# DebugCAN_v2.net
KiCad netlist of a schematic drawn in EAGLE
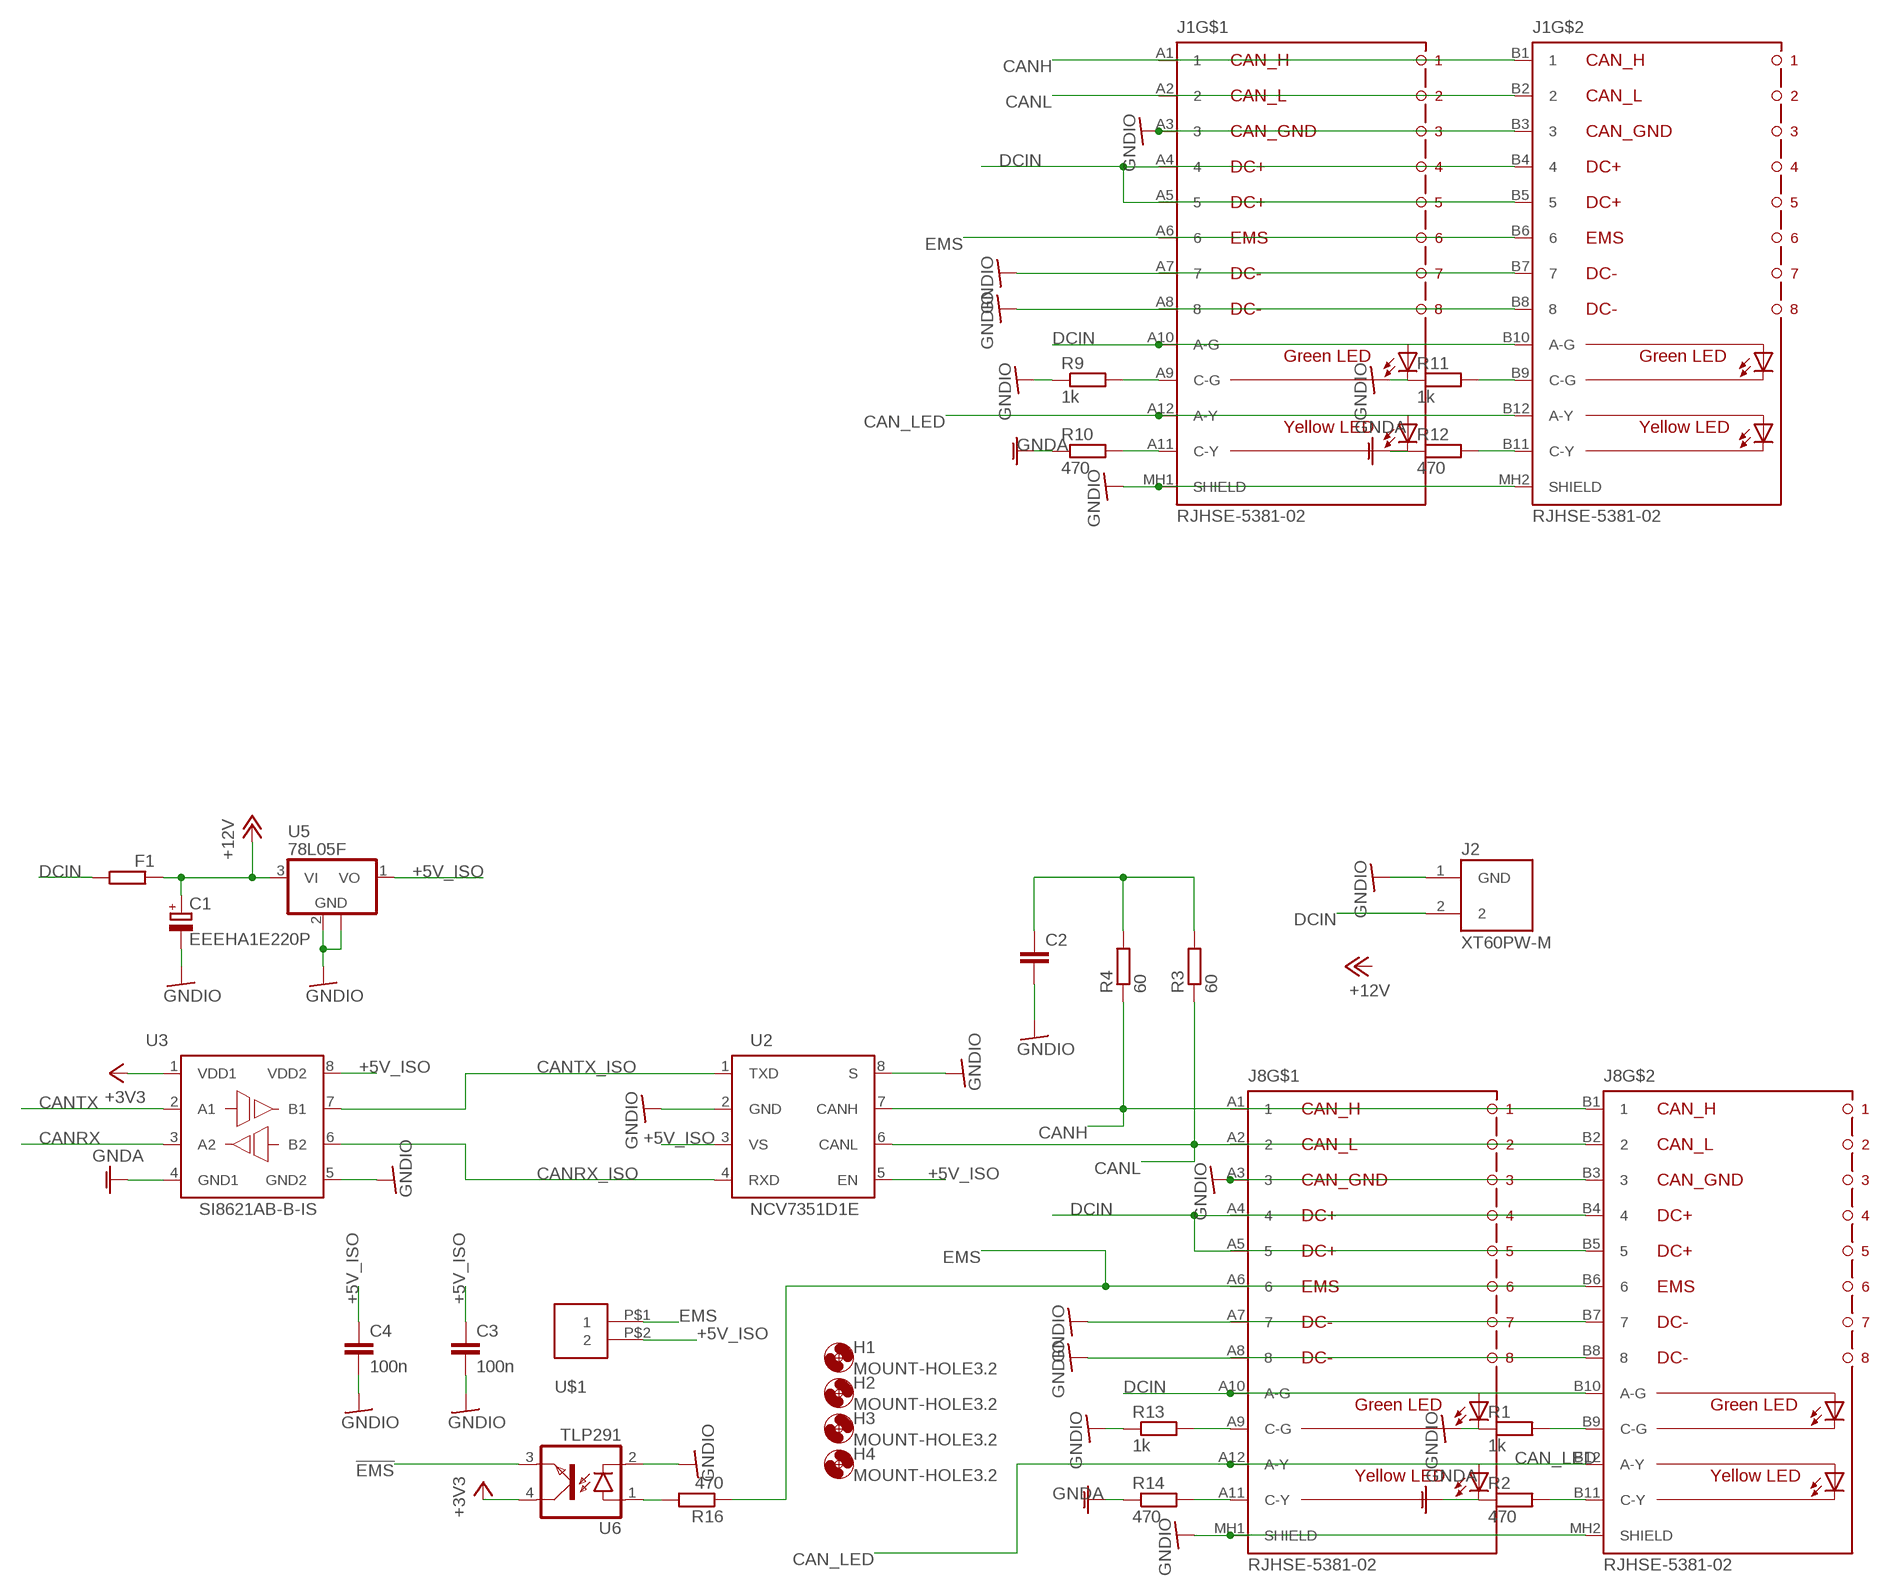
[diagram p0: schematic, sheet 1]
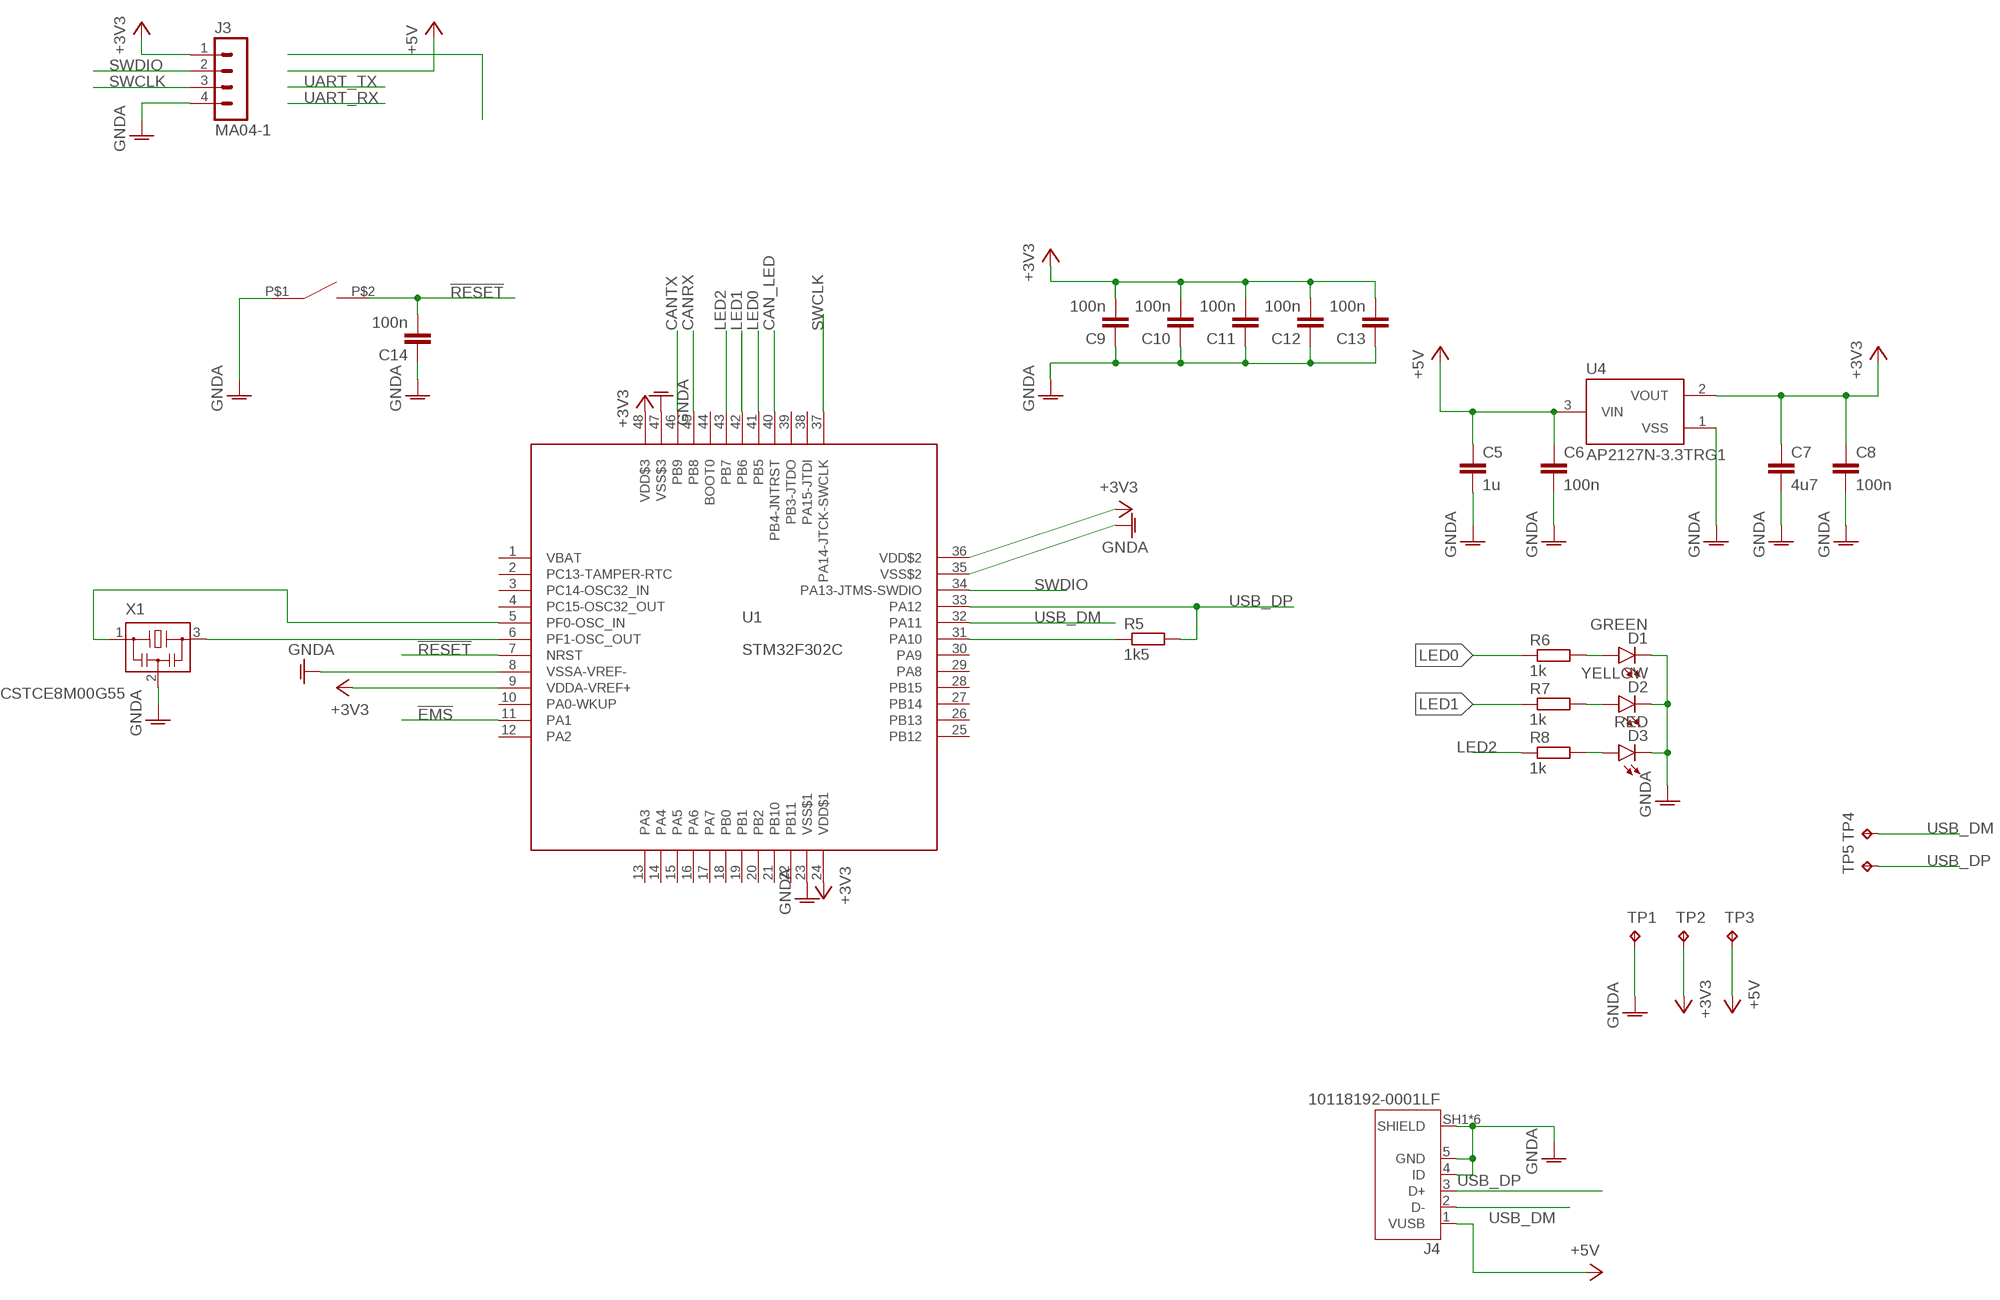
[diagram p1: schematic, sheet 2]

(export (version "E")
  (design (tool "Eeschema 10.0.6"))
  (components
    (comp (ref "C1")
      (value "EEEHA1E220P")
      (footprint "eagle-import:153CLV-0605")
      (libsource (lib "eagle-import") (part "CPOL-EU153CLV-0605"))
    )
    (comp (ref "C2")
      (value "C-EUC0603")
      (footprint "eagle-import:C0603")
      (libsource (lib "eagle-import") (part "rcl_334_C-EUC0603"))
    )
    (comp (ref "C3")
      (value "100n")
      (footprint "eagle-import:C0603")
      (libsource (lib "eagle-import") (part "rcl_334_C-EUC0603"))
    )
    (comp (ref "C4")
      (value "100n")
      (footprint "eagle-import:C0603")
      (libsource (lib "eagle-import") (part "rcl_334_C-EUC0603"))
    )
    (comp (ref "F1")
      (value "R-EU_R1206")
      (footprint "eagle-import:R1206")
      (libsource (lib "eagle-import") (part "rcl_334_R-EU_R1206"))
    )
    (comp (ref "H1")
      (value "MOUNT-HOLE3.2")
      (footprint "eagle-import:3,2")
      (libsource (lib "eagle-import") (part "MOUNT-HOLE3.2"))
    )
    (comp (ref "H2")
      (value "MOUNT-HOLE3.2")
      (footprint "eagle-import:3,2")
      (libsource (lib "eagle-import") (part "MOUNT-HOLE3.2"))
    )
    (comp (ref "H3")
      (value "MOUNT-HOLE3.2")
      (footprint "eagle-import:3,2")
      (libsource (lib "eagle-import") (part "MOUNT-HOLE3.2"))
    )
    (comp (ref "H4")
      (value "MOUNT-HOLE3.2")
      (footprint "eagle-import:3,2")
      (libsource (lib "eagle-import") (part "MOUNT-HOLE3.2"))
    )
    (comp (ref "J1")
      (value "RJHSE-5381-02")
      (footprint "eagle-import:RJHSE538102")
      (fields (field (name "MOUSER_PART_NUMBER") "523-RJHSE-5381-02"))
      (libsource (lib "eagle-import") (part "RJHSE-5381-02"))
    )
    (comp (ref "J2")
      (value "XT60PW-M")
      (footprint "eagle-import:AMASS_XT60PW-M")
      (fields (field (name "MF") "AMASS") (field (name "MP") "XT60PW-M "))
      (libsource (lib "eagle-import") (part "XT60PW-M"))
    )
    (comp (ref "J8")
      (value "RJHSE-5381-02")
      (footprint "eagle-import:RJHSE538102")
      (fields (field (name "MOUSER_PART_NUMBER") "523-RJHSE-5381-02"))
      (libsource (lib "eagle-import") (part "RJHSE-5381-02"))
    )
    (comp (ref "R1")
      (value "1k")
      (footprint "eagle-import:R0603")
      (libsource (lib "eagle-import") (part "rcl_334_R-EU_R0603"))
    )
    (comp (ref "R2")
      (value "470")
      (footprint "eagle-import:R0603")
      (libsource (lib "eagle-import") (part "rcl_334_R-EU_R0603"))
    )
    (comp (ref "R3")
      (value "60")
      (footprint "eagle-import:R0603")
      (libsource (lib "eagle-import") (part "rcl_334_R-EU_R0603"))
    )
    (comp (ref "R4")
      (value "60")
      (footprint "eagle-import:R0603")
      (libsource (lib "eagle-import") (part "rcl_334_R-EU_R0603"))
    )
    (comp (ref "R9")
      (value "1k")
      (footprint "eagle-import:R0603")
      (libsource (lib "eagle-import") (part "rcl_334_R-EU_R0603"))
    )
    (comp (ref "R10")
      (value "470")
      (footprint "eagle-import:R0603")
      (libsource (lib "eagle-import") (part "rcl_334_R-EU_R0603"))
    )
    (comp (ref "R11")
      (value "1k")
      (footprint "eagle-import:R0603")
      (libsource (lib "eagle-import") (part "rcl_334_R-EU_R0603"))
    )
    (comp (ref "R12")
      (value "470")
      (footprint "eagle-import:R0603")
      (libsource (lib "eagle-import") (part "rcl_334_R-EU_R0603"))
    )
    (comp (ref "R13")
      (value "1k")
      (footprint "eagle-import:R0603")
      (libsource (lib "eagle-import") (part "rcl_334_R-EU_R0603"))
    )
    (comp (ref "R14")
      (value "470")
      (footprint "eagle-import:R0603")
      (libsource (lib "eagle-import") (part "rcl_334_R-EU_R0603"))
    )
    (comp (ref "R16")
      (value "470")
      (footprint "eagle-import:R0603")
      (libsource (lib "eagle-import") (part "rcl_334_R-EU_R0603"))
    )
    (comp (ref "U$1")
      (value "XH-2-STRAIGHT")
      (footprint "eagle-import:CON-XH-2-STRAIGHT")
      (libsource (lib "eagle-import") (part "XH-2-STRAIGHT"))
    )
    (comp (ref "U2")
      (value "NCV7351D1E")
      (footprint "eagle-import:SO08")
      (libsource (lib "eagle-import") (part "NCV7351D1E"))
    )
    (comp (ref "U3")
      (value "SI8621AB-B-IS")
      (footprint "eagle-import:SO08")
      (libsource (lib "eagle-import") (part "SI8621AB-B-IS"))
    )
    (comp (ref "U5")
      (value "78L05F")
      (footprint "eagle-import:SOT89")
      (libsource (lib "eagle-import") (part "78LF05"))
    )
    (comp (ref "U6")
      (value "TLP291")
      (footprint "eagle-import:MINI-FLAT-4")
      (libsource (lib "eagle-import") (part "TLP291"))
    )
    (comp (ref "C5")
      (value "1u")
      (footprint "eagle-import:C0603")
      (libsource (lib "eagle-import") (part "C-EUC0603"))
    )
    (comp (ref "C6")
      (value "100n")
      (footprint "eagle-import:C0603")
      (libsource (lib "eagle-import") (part "C-EUC0603"))
    )
    (comp (ref "C7")
      (value "4u7")
      (footprint "eagle-import:C0805")
      (libsource (lib "eagle-import") (part "C-EUC0805"))
    )
    (comp (ref "C8")
      (value "100n")
      (footprint "eagle-import:C0603")
      (libsource (lib "eagle-import") (part "C-EUC0603"))
    )
    (comp (ref "C9")
      (value "100n")
      (footprint "eagle-import:C0603")
      (libsource (lib "eagle-import") (part "C-EUC0603"))
    )
    (comp (ref "C10")
      (value "100n")
      (footprint "eagle-import:C0603")
      (libsource (lib "eagle-import") (part "C-EUC0603"))
    )
    (comp (ref "C11")
      (value "100n")
      (footprint "eagle-import:C0603")
      (libsource (lib "eagle-import") (part "C-EUC0603"))
    )
    (comp (ref "C12")
      (value "100n")
      (footprint "eagle-import:C0603")
      (libsource (lib "eagle-import") (part "C-EUC0603"))
    )
    (comp (ref "C13")
      (value "100n")
      (footprint "eagle-import:C0603")
      (libsource (lib "eagle-import") (part "C-EUC0603"))
    )
    (comp (ref "C14")
      (value "100n")
      (footprint "eagle-import:C0603")
      (libsource (lib "eagle-import") (part "C-EUC0603"))
    )
    (comp (ref "D1")
      (value "GREEN")
      (footprint "eagle-import:CHIPLED_0805")
      (libsource (lib "eagle-import") (part "LEDCHIPLED_0805"))
    )
    (comp (ref "D2")
      (value "YELLOW")
      (footprint "eagle-import:CHIPLED_0805")
      (libsource (lib "eagle-import") (part "LEDCHIPLED_0805"))
    )
    (comp (ref "D3")
      (value "RED")
      (footprint "eagle-import:CHIPLED_0805")
      (libsource (lib "eagle-import") (part "LEDCHIPLED_0805"))
    )
    (comp (ref "J3")
      (value "MA04-1")
      (footprint "eagle-import:MA04-1")
      (libsource (lib "eagle-import") (part "MA04-1"))
    )
    (comp (ref "J4")
      (value "10118192-0001LF")
      (footprint "eagle-import:AMPHENOL_10118192-0001LF")
      (fields (field (name "DIGI-KEY_PART_NUMBER") "609-4613-1-ND") (field (name "MF") "Amphenol ICC"))
      (libsource (lib "eagle-import") (part "10118192-0001LF"))
    )
    (comp (ref "R5")
      (value "1k5")
      (footprint "eagle-import:R0603")
      (libsource (lib "eagle-import") (part "R-EU_R0603"))
    )
    (comp (ref "R6")
      (value "1k")
      (footprint "eagle-import:R0603")
      (libsource (lib "eagle-import") (part "R-EU_R0603"))
    )
    (comp (ref "R7")
      (value "1k")
      (footprint "eagle-import:R0603")
      (libsource (lib "eagle-import") (part "R-EU_R0603"))
    )
    (comp (ref "R8")
      (value "1k")
      (footprint "eagle-import:R0603")
      (libsource (lib "eagle-import") (part "R-EU_R0603"))
    )
    (comp (ref "S1")
      (value "SWITCH_TACTILETOP")
      (footprint "eagle-import:SWITCH_TACTILE_3X6")
      (libsource (lib "eagle-import") (part "SWITCH_TACTILETOP"))
    )
    (comp (ref "TP1")
      (value "TPB1,27")
      (footprint "eagle-import:B1,27")
      (libsource (lib "eagle-import") (part "TPB1,27"))
    )
    (comp (ref "TP2")
      (value "TPB1,27")
      (footprint "eagle-import:B1,27")
      (libsource (lib "eagle-import") (part "TPB1,27"))
    )
    (comp (ref "TP3")
      (value "TPB1,27")
      (footprint "eagle-import:B1,27")
      (libsource (lib "eagle-import") (part "TPB1,27"))
    )
    (comp (ref "TP4")
      (value "TPB1,27")
      (footprint "eagle-import:B1,27")
      (libsource (lib "eagle-import") (part "TPB1,27"))
    )
    (comp (ref "TP5")
      (value "TPB1,27")
      (footprint "eagle-import:B1,27")
      (libsource (lib "eagle-import") (part "TPB1,27"))
    )
    (comp (ref "U1")
      (value "STM32F302C")
      (footprint "eagle-import:LQFP48")
      (libsource (lib "eagle-import") (part "STM32F303C"))
    )
    (comp (ref "U4")
      (value "AP2127N-3.3TRG1")
      (footprint "eagle-import:SOT95P240X110-3")
      (libsource (lib "eagle-import") (part "XC6206"))
    )
    (comp (ref "X1")
      (value "CSTCE8M00G55")
      (footprint "eagle-import:CSTCE8M00G55")
      (libsource (lib "eagle-import") (part "CSTCE8M00G55"))
    )
  )
  (nets
    (net (code "1") (name "+3V3") (class "Default")
      (node (ref "C10") (pin "2") (pinfunction "2_2") (pintype "passive"))
      (node (ref "C11") (pin "2") (pinfunction "2_2") (pintype "passive"))
      (node (ref "C12") (pin "2") (pinfunction "2_2") (pintype "passive"))
      (node (ref "C13") (pin "2") (pinfunction "2_2") (pintype "passive"))
      (node (ref "C7") (pin "1") (pinfunction "1_1") (pintype "passive"))
      (node (ref "C8") (pin "1") (pinfunction "1_1") (pintype "passive"))
      (node (ref "C9") (pin "2") (pinfunction "2_2") (pintype "passive"))
      (node (ref "J3") (pin "1") (pinfunction "1_1") (pintype "passive"))
      (node (ref "TP2") (pin "TP") (pinfunction "TP_TP") (pintype "input"))
      (node (ref "U1") (pin "24") (pinfunction "VDD$1_24") (pintype "passive"))
      (node (ref "U1") (pin "36") (pinfunction "VDD$2_36") (pintype "passive"))
      (node (ref "U1") (pin "48") (pinfunction "VDD$3_48") (pintype "passive"))
      (node (ref "U1") (pin "9") (pinfunction "VDDA-VREF+_9") (pintype "bidirectional"))
      (node (ref "U3") (pin "1") (pinfunction "VDD1_1") (pintype "power_in"))
      (node (ref "U4") (pin "2") (pinfunction "VOUT_2") (pintype "bidirectional"))
      (node (ref "U6") (pin "4") (pinfunction "COL_4") (pintype "passive"))
    )
    (net (code "2") (name "+5V") (class "Default")
      (node (ref "C5") (pin "1") (pinfunction "1_1") (pintype "passive"))
      (node (ref "C6") (pin "1") (pinfunction "1_1") (pintype "passive"))
      (node (ref "J4") (pin "1") (pinfunction "VUSB_1") (pintype "passive"))
      (node (ref "TP3") (pin "TP") (pinfunction "TP_TP") (pintype "input"))
      (node (ref "U4") (pin "3") (pinfunction "VIN_3") (pintype "bidirectional"))
    )
    (net (code "3") (name "+5V_ISO") (class "Default")
      (node (ref "C3") (pin "1") (pinfunction "1_1") (pintype "passive"))
      (node (ref "C4") (pin "1") (pinfunction "1_1") (pintype "passive"))
      (node (ref "U$1") (pin "P$2") (pinfunction "2_P$2") (pintype "bidirectional"))
      (node (ref "U2") (pin "3") (pinfunction "VS_3") (pintype "power_in"))
      (node (ref "U2") (pin "5") (pinfunction "EN_5") (pintype "input"))
      (node (ref "U3") (pin "8") (pinfunction "VDD2_8") (pintype "power_in"))
      (node (ref "U5") (pin "1") (pinfunction "VO_1") (pintype "passive"))
    )
    (net (code "4") (name "+12V") (class "Default")
      (node (ref "C1") (pin "+") (pinfunction "+_+") (pintype "passive"))
      (node (ref "F1") (pin "1") (pinfunction "1_1") (pintype "passive"))
      (node (ref "U5") (pin "3") (pinfunction "VI_3") (pintype "input"))
    )
    (net (code "5") (name "CANH") (class "Default")
      (node (ref "J1") (pin "A1") (pinfunction "1_A1") (pintype "input"))
      (node (ref "J1") (pin "B1") (pinfunction "1_B1") (pintype "input"))
      (node (ref "J8") (pin "A1") (pinfunction "1_A1") (pintype "input"))
      (node (ref "J8") (pin "B1") (pinfunction "1_B1") (pintype "input"))
      (node (ref "R4") (pin "1") (pinfunction "1_1") (pintype "passive"))
      (node (ref "U2") (pin "7") (pinfunction "CANH_7") (pintype "output"))
    )
    (net (code "6") (name "CANL") (class "Default")
      (node (ref "J1") (pin "A2") (pinfunction "2_A2") (pintype "input"))
      (node (ref "J1") (pin "B2") (pinfunction "2_B2") (pintype "input"))
      (node (ref "J8") (pin "A2") (pinfunction "2_A2") (pintype "input"))
      (node (ref "J8") (pin "B2") (pinfunction "2_B2") (pintype "input"))
      (node (ref "R3") (pin "1") (pinfunction "1_1") (pintype "passive"))
      (node (ref "U2") (pin "6") (pinfunction "CANL_6") (pintype "output"))
    )
    (net (code "7") (name "CANRX") (class "Default")
      (node (ref "U1") (pin "45") (pinfunction "PB8_45") (pintype "bidirectional"))
      (node (ref "U3") (pin "3") (pinfunction "A2_3") (pintype "output"))
    )
    (net (code "8") (name "CANRX_ISO") (class "Default")
      (node (ref "U2") (pin "4") (pinfunction "RXD_4") (pintype "output"))
      (node (ref "U3") (pin "6") (pinfunction "B2_6") (pintype "output"))
    )
    (net (code "9") (name "CANTX") (class "Default")
      (node (ref "U1") (pin "46") (pinfunction "PB9_46") (pintype "bidirectional"))
      (node (ref "U3") (pin "2") (pinfunction "A1_2") (pintype "input"))
    )
    (net (code "10") (name "CANTX_ISO") (class "Default")
      (node (ref "U2") (pin "1") (pinfunction "TXD_1") (pintype "input"))
      (node (ref "U3") (pin "7") (pinfunction "B1_7") (pintype "output"))
    )
    (net (code "11") (name "CAN_LED") (class "Default")
      (node (ref "J1") (pin "A12") (pinfunction "A-Y_A12") (pintype "passive"))
      (node (ref "J1") (pin "B12") (pinfunction "A-Y_B12") (pintype "passive"))
      (node (ref "J8") (pin "A12") (pinfunction "A-Y_A12") (pintype "passive"))
      (node (ref "J8") (pin "B12") (pinfunction "A-Y_B12") (pintype "passive"))
      (node (ref "U1") (pin "40") (pinfunction "PB4-JNTRST_40") (pintype "bidirectional"))
    )
    (net (code "12") (name "DCIN") (class "Default")
      (node (ref "F1") (pin "2") (pinfunction "2_2") (pintype "passive"))
      (node (ref "J1") (pin "A10") (pinfunction "A-G_A10") (pintype "passive"))
      (node (ref "J1") (pin "A4") (pinfunction "4_A4") (pintype "input"))
      (node (ref "J1") (pin "A5") (pinfunction "5_A5") (pintype "input"))
      (node (ref "J1") (pin "B10") (pinfunction "A-G_B10") (pintype "passive"))
      (node (ref "J1") (pin "B4") (pinfunction "4_B4") (pintype "input"))
      (node (ref "J1") (pin "B5") (pinfunction "5_B5") (pintype "input"))
      (node (ref "J2") (pin "2") (pinfunction "2_2") (pintype "passive"))
      (node (ref "J8") (pin "A10") (pinfunction "A-G_A10") (pintype "passive"))
      (node (ref "J8") (pin "A4") (pinfunction "4_A4") (pintype "input"))
      (node (ref "J8") (pin "A5") (pinfunction "5_A5") (pintype "input"))
      (node (ref "J8") (pin "B10") (pinfunction "A-G_B10") (pintype "passive"))
      (node (ref "J8") (pin "B4") (pinfunction "4_B4") (pintype "input"))
      (node (ref "J8") (pin "B5") (pinfunction "5_B5") (pintype "input"))
    )
    (net (code "13") (name "EMS") (class "Default")
      (node (ref "J1") (pin "A6") (pinfunction "6_A6") (pintype "input"))
      (node (ref "J1") (pin "B6") (pinfunction "6_B6") (pintype "input"))
      (node (ref "J8") (pin "A6") (pinfunction "6_A6") (pintype "input"))
      (node (ref "J8") (pin "B6") (pinfunction "6_B6") (pintype "input"))
      (node (ref "R16") (pin "1") (pinfunction "1_1") (pintype "passive"))
      (node (ref "U$1") (pin "P$1") (pinfunction "1_P$1") (pintype "bidirectional"))
    )
    (net (code "14") (name "GNDA") (class "Default")
      (node (ref "C10") (pin "1") (pinfunction "1_1") (pintype "passive"))
      (node (ref "C11") (pin "1") (pinfunction "1_1") (pintype "passive"))
      (node (ref "C12") (pin "1") (pinfunction "1_1") (pintype "passive"))
      (node (ref "C13") (pin "1") (pinfunction "1_1") (pintype "passive"))
      (node (ref "C14") (pin "1") (pinfunction "1_1") (pintype "passive"))
      (node (ref "C5") (pin "2") (pinfunction "2_2") (pintype "passive"))
      (node (ref "C6") (pin "2") (pinfunction "2_2") (pintype "passive"))
      (node (ref "C7") (pin "2") (pinfunction "2_2") (pintype "passive"))
      (node (ref "C8") (pin "2") (pinfunction "2_2") (pintype "passive"))
      (node (ref "C9") (pin "1") (pinfunction "1_1") (pintype "passive"))
      (node (ref "D1") (pin "C") (pinfunction "C_C") (pintype "passive"))
      (node (ref "D2") (pin "C") (pinfunction "C_C") (pintype "passive"))
      (node (ref "D3") (pin "C") (pinfunction "C_C") (pintype "passive"))
      (node (ref "J3") (pin "4") (pinfunction "4_4") (pintype "passive"))
      (node (ref "J4") (pin "4") (pinfunction "ID_4") (pintype "passive"))
      (node (ref "J4") (pin "5") (pinfunction "GND_5") (pintype "passive"))
      (node (ref "J4") (pin "SH1") (pinfunction "SHIELD_SH1") (pintype "passive"))
      (node (ref "J4") (pin "SH2") (pinfunction "SHIELD_SH2") (pintype "passive"))
      (node (ref "J4") (pin "SH3") (pinfunction "SHIELD_SH3") (pintype "passive"))
      (node (ref "J4") (pin "SH4") (pinfunction "SHIELD_SH4") (pintype "passive"))
      (node (ref "J4") (pin "SH5") (pinfunction "SHIELD_SH5") (pintype "passive"))
      (node (ref "J4") (pin "SH6") (pinfunction "SHIELD_SH6") (pintype "passive"))
      (node (ref "R10") (pin "1") (pinfunction "1_1") (pintype "passive"))
      (node (ref "R12") (pin "1") (pinfunction "1_1") (pintype "passive"))
      (node (ref "R14") (pin "1") (pinfunction "1_1") (pintype "passive"))
      (node (ref "R2") (pin "1") (pinfunction "1_1") (pintype "passive"))
      (node (ref "S1") (pin "P$1") (pinfunction "1_P$1") (pintype "bidirectional"))
      (node (ref "TP1") (pin "TP") (pinfunction "TP_TP") (pintype "input"))
      (node (ref "U1") (pin "23") (pinfunction "VSS$1_23") (pintype "passive"))
      (node (ref "U1") (pin "35") (pinfunction "VSS$2_35") (pintype "passive"))
      (node (ref "U1") (pin "47") (pinfunction "VSS$3_47") (pintype "passive"))
      (node (ref "U1") (pin "8") (pinfunction "VSSA-VREF-_8") (pintype "bidirectional"))
      (node (ref "U3") (pin "4") (pinfunction "GND1_4") (pintype "power_in"))
      (node (ref "U4") (pin "1") (pinfunction "VSS_1") (pintype "bidirectional"))
      (node (ref "X1") (pin "2") (pinfunction "2_2") (pintype "passive"))
    )
    (net (code "15") (name "GNDIO") (class "Default")
      (node (ref "C1") (pin "-") (pinfunction "-_-") (pintype "passive"))
      (node (ref "C2") (pin "2") (pinfunction "2_2") (pintype "passive"))
      (node (ref "C3") (pin "2") (pinfunction "2_2") (pintype "passive"))
      (node (ref "C4") (pin "2") (pinfunction "2_2") (pintype "passive"))
      (node (ref "J1") (pin "A3") (pinfunction "3_A3") (pintype "input"))
      (node (ref "J1") (pin "A7") (pinfunction "7_A7") (pintype "input"))
      (node (ref "J1") (pin "A8") (pinfunction "8_A8") (pintype "input"))
      (node (ref "J1") (pin "B3") (pinfunction "3_B3") (pintype "input"))
      (node (ref "J1") (pin "B7") (pinfunction "7_B7") (pintype "input"))
      (node (ref "J1") (pin "B8") (pinfunction "8_B8") (pintype "input"))
      (node (ref "J1") (pin "MH1") (pinfunction "SHIELD_MH1") (pintype "passive"))
      (node (ref "J1") (pin "MH2") (pinfunction "SHIELD_MH2") (pintype "passive"))
      (node (ref "J2") (pin "1") (pinfunction "GND_1") (pintype "passive"))
      (node (ref "J8") (pin "A3") (pinfunction "3_A3") (pintype "input"))
      (node (ref "J8") (pin "A7") (pinfunction "7_A7") (pintype "input"))
      (node (ref "J8") (pin "A8") (pinfunction "8_A8") (pintype "input"))
      (node (ref "J8") (pin "B3") (pinfunction "3_B3") (pintype "input"))
      (node (ref "J8") (pin "B7") (pinfunction "7_B7") (pintype "input"))
      (node (ref "J8") (pin "B8") (pinfunction "8_B8") (pintype "input"))
      (node (ref "J8") (pin "MH1") (pinfunction "SHIELD_MH1") (pintype "passive"))
      (node (ref "J8") (pin "MH2") (pinfunction "SHIELD_MH2") (pintype "passive"))
      (node (ref "R1") (pin "1") (pinfunction "1_1") (pintype "passive"))
      (node (ref "R11") (pin "1") (pinfunction "1_1") (pintype "passive"))
      (node (ref "R13") (pin "1") (pinfunction "1_1") (pintype "passive"))
      (node (ref "R9") (pin "1") (pinfunction "1_1") (pintype "passive"))
      (node (ref "U2") (pin "2") (pinfunction "GND_2") (pintype "power_in"))
      (node (ref "U2") (pin "8") (pinfunction "S_8") (pintype "input"))
      (node (ref "U3") (pin "5") (pinfunction "GND2_5") (pintype "power_in"))
      (node (ref "U5") (pin "2") (pinfunction "GND_2") (pintype "passive"))
      (node (ref "U5") (pin "2@1") (pinfunction "GND_2@1") (pintype "passive"))
      (node (ref "U6") (pin "2") (pinfunction "C_2") (pintype "passive"))
    )
    (net (code "16") (name "LED0") (class "Default")
      (node (ref "R6") (pin "1") (pinfunction "1_1") (pintype "passive"))
      (node (ref "U1") (pin "41") (pinfunction "PB5_41") (pintype "bidirectional"))
    )
    (net (code "17") (name "LED1") (class "Default")
      (node (ref "R7") (pin "1") (pinfunction "1_1") (pintype "passive"))
      (node (ref "U1") (pin "42") (pinfunction "PB6_42") (pintype "bidirectional"))
    )
    (net (code "18") (name "LED2") (class "Default")
      (node (ref "R8") (pin "1") (pinfunction "1_1") (pintype "passive"))
      (node (ref "U1") (pin "43") (pinfunction "PB7_43") (pintype "bidirectional"))
    )
    (net (code "19") (name "Net-(C2-Pad1)") (class "Default")
      (node (ref "C2") (pin "1") (pinfunction "1_1") (pintype "passive"))
      (node (ref "R3") (pin "2") (pinfunction "2_2") (pintype "passive"))
      (node (ref "R4") (pin "2") (pinfunction "2_2") (pintype "passive"))
    )
    (net (code "20") (name "Net-(D1-PadA)") (class "Default")
      (node (ref "D1") (pin "A") (pinfunction "A_A") (pintype "passive"))
      (node (ref "R6") (pin "2") (pinfunction "2_2") (pintype "passive"))
    )
    (net (code "21") (name "Net-(D2-PadA)") (class "Default")
      (node (ref "D2") (pin "A") (pinfunction "A_A") (pintype "passive"))
      (node (ref "R7") (pin "2") (pinfunction "2_2") (pintype "passive"))
    )
    (net (code "22") (name "Net-(D3-PadA)") (class "Default")
      (node (ref "D3") (pin "A") (pinfunction "A_A") (pintype "passive"))
      (node (ref "R8") (pin "2") (pinfunction "2_2") (pintype "passive"))
    )
    (net (code "23") (name "Net-(J1A-C-G)") (class "Default")
      (node (ref "J1") (pin "A9") (pinfunction "C-G_A9") (pintype "passive"))
      (node (ref "R9") (pin "2") (pinfunction "2_2") (pintype "passive"))
    )
    (net (code "24") (name "Net-(J1A-C-Y)") (class "Default")
      (node (ref "J1") (pin "A11") (pinfunction "C-Y_A11") (pintype "passive"))
      (node (ref "R10") (pin "2") (pinfunction "2_2") (pintype "passive"))
    )
    (net (code "25") (name "Net-(J1B-C-G)") (class "Default")
      (node (ref "J1") (pin "B9") (pinfunction "C-G_B9") (pintype "passive"))
      (node (ref "R11") (pin "2") (pinfunction "2_2") (pintype "passive"))
    )
    (net (code "26") (name "Net-(J1B-C-Y)") (class "Default")
      (node (ref "J1") (pin "B11") (pinfunction "C-Y_B11") (pintype "passive"))
      (node (ref "R12") (pin "2") (pinfunction "2_2") (pintype "passive"))
    )
    (net (code "27") (name "Net-(J8A-C-G)") (class "Default")
      (node (ref "J8") (pin "A9") (pinfunction "C-G_A9") (pintype "passive"))
      (node (ref "R13") (pin "2") (pinfunction "2_2") (pintype "passive"))
    )
    (net (code "28") (name "Net-(J8A-C-Y)") (class "Default")
      (node (ref "J8") (pin "A11") (pinfunction "C-Y_A11") (pintype "passive"))
      (node (ref "R14") (pin "2") (pinfunction "2_2") (pintype "passive"))
    )
    (net (code "29") (name "Net-(J8B-C-G)") (class "Default")
      (node (ref "J8") (pin "B9") (pinfunction "C-G_B9") (pintype "passive"))
      (node (ref "R1") (pin "2") (pinfunction "2_2") (pintype "passive"))
    )
    (net (code "30") (name "Net-(J8B-C-Y)") (class "Default")
      (node (ref "J8") (pin "B11") (pinfunction "C-Y_B11") (pintype "passive"))
      (node (ref "R2") (pin "2") (pinfunction "2_2") (pintype "passive"))
    )
    (net (code "31") (name "Net-(U1-PA10)") (class "Default")
      (node (ref "R5") (pin "1") (pinfunction "1_1") (pintype "passive"))
      (node (ref "U1") (pin "31") (pinfunction "PA10_31") (pintype "bidirectional"))
    )
    (net (code "32") (name "Net-(U1-PF0-OSC_IN)") (class "Default")
      (node (ref "U1") (pin "5") (pinfunction "PF0-OSC_IN_5") (pintype "input"))
      (node (ref "X1") (pin "1") (pinfunction "1_1") (pintype "passive"))
    )
    (net (code "33") (name "Net-(U1-PF1-OSC_OUT)") (class "Default")
      (node (ref "U1") (pin "6") (pinfunction "PF1-OSC_OUT_6") (pintype "output"))
      (node (ref "X1") (pin "3") (pinfunction "3_3") (pintype "passive"))
    )
    (net (code "34") (name "Net-(U6-A)") (class "Default")
      (node (ref "R16") (pin "2") (pinfunction "2_2") (pintype "passive"))
      (node (ref "U6") (pin "1") (pinfunction "A_1") (pintype "passive"))
    )
    (net (code "35") (name "SWCLK") (class "Default")
      (node (ref "J3") (pin "3") (pinfunction "3_3") (pintype "passive"))
      (node (ref "U1") (pin "37") (pinfunction "PA14-JTCK-SWCLK_37") (pintype "bidirectional"))
    )
    (net (code "36") (name "SWDIO") (class "Default")
      (node (ref "J3") (pin "2") (pinfunction "2_2") (pintype "passive"))
      (node (ref "U1") (pin "34") (pinfunction "PA13-JTMS-SWDIO_34") (pintype "bidirectional"))
    )
    (net (code "39") (name "USB_DM") (class "Default")
      (node (ref "J4") (pin "2") (pinfunction "D-_2") (pintype "passive"))
      (node (ref "TP4") (pin "TP") (pinfunction "TP_TP") (pintype "input"))
      (node (ref "U1") (pin "32") (pinfunction "PA11_32") (pintype "bidirectional"))
    )
    (net (code "40") (name "USB_DP") (class "Default")
      (node (ref "J4") (pin "3") (pinfunction "D+_3") (pintype "passive"))
      (node (ref "R5") (pin "2") (pinfunction "2_2") (pintype "passive"))
      (node (ref "TP5") (pin "TP") (pinfunction "TP_TP") (pintype "input"))
      (node (ref "U1") (pin "33") (pinfunction "PA12_33") (pintype "bidirectional"))
    )
    (net (code "41") (name "unconnected-(U1-BOOT0-Pad44)") (class "Default")
      (node (ref "U1") (pin "44") (pinfunction "BOOT0_44") (pintype "input"))
    )
    (net (code "42") (name "unconnected-(U1-PA0-WKUP-Pad10)") (class "Default")
      (node (ref "U1") (pin "10") (pinfunction "PA0-WKUP_10") (pintype "bidirectional"))
    )
    (net (code "43") (name "unconnected-(U1-PA2-Pad12)") (class "Default")
      (node (ref "U1") (pin "12") (pinfunction "PA2_12") (pintype "bidirectional"))
    )
    (net (code "44") (name "unconnected-(U1-PA3-Pad13)") (class "Default")
      (node (ref "U1") (pin "13") (pinfunction "PA3_13") (pintype "bidirectional"))
    )
    (net (code "45") (name "unconnected-(U1-PA4-Pad14)") (class "Default")
      (node (ref "U1") (pin "14") (pinfunction "PA4_14") (pintype "bidirectional"))
    )
    (net (code "46") (name "unconnected-(U1-PA5-Pad15)") (class "Default")
      (node (ref "U1") (pin "15") (pinfunction "PA5_15") (pintype "bidirectional"))
    )
    (net (code "47") (name "unconnected-(U1-PA6-Pad16)") (class "Default")
      (node (ref "U1") (pin "16") (pinfunction "PA6_16") (pintype "bidirectional"))
    )
    (net (code "48") (name "unconnected-(U1-PA7-Pad17)") (class "Default")
      (node (ref "U1") (pin "17") (pinfunction "PA7_17") (pintype "bidirectional"))
    )
    (net (code "49") (name "unconnected-(U1-PA8-Pad29)") (class "Default")
      (node (ref "U1") (pin "29") (pinfunction "PA8_29") (pintype "bidirectional"))
    )
    (net (code "50") (name "unconnected-(U1-PA9-Pad30)") (class "Default")
      (node (ref "U1") (pin "30") (pinfunction "PA9_30") (pintype "bidirectional"))
    )
    (net (code "51") (name "unconnected-(U1-PA15-JTDI-Pad38)") (class "Default")
      (node (ref "U1") (pin "38") (pinfunction "PA15-JTDI_38") (pintype "bidirectional"))
    )
    (net (code "52") (name "unconnected-(U1-PB0-Pad18)") (class "Default")
      (node (ref "U1") (pin "18") (pinfunction "PB0_18") (pintype "bidirectional"))
    )
    (net (code "53") (name "unconnected-(U1-PB1-Pad19)") (class "Default")
      (node (ref "U1") (pin "19") (pinfunction "PB1_19") (pintype "bidirectional"))
    )
    (net (code "54") (name "unconnected-(U1-PB2-Pad20)") (class "Default")
      (node (ref "U1") (pin "20") (pinfunction "PB2_20") (pintype "bidirectional"))
    )
    (net (code "55") (name "unconnected-(U1-PB3-JTDO-Pad39)") (class "Default")
      (node (ref "U1") (pin "39") (pinfunction "PB3-JTDO_39") (pintype "bidirectional"))
    )
    (net (code "56") (name "unconnected-(U1-PB10-Pad21)") (class "Default")
      (node (ref "U1") (pin "21") (pinfunction "PB10_21") (pintype "bidirectional"))
    )
    (net (code "57") (name "unconnected-(U1-PB11-Pad22)") (class "Default")
      (node (ref "U1") (pin "22") (pinfunction "PB11_22") (pintype "bidirectional"))
    )
    (net (code "58") (name "unconnected-(U1-PB12-Pad25)") (class "Default")
      (node (ref "U1") (pin "25") (pinfunction "PB12_25") (pintype "bidirectional"))
    )
    (net (code "59") (name "unconnected-(U1-PB13-Pad26)") (class "Default")
      (node (ref "U1") (pin "26") (pinfunction "PB13_26") (pintype "bidirectional"))
    )
    (net (code "60") (name "unconnected-(U1-PB14-Pad27)") (class "Default")
      (node (ref "U1") (pin "27") (pinfunction "PB14_27") (pintype "bidirectional"))
    )
    (net (code "61") (name "unconnected-(U1-PB15-Pad28)") (class "Default")
      (node (ref "U1") (pin "28") (pinfunction "PB15_28") (pintype "bidirectional"))
    )
    (net (code "62") (name "unconnected-(U1-PC13-TAMPER-RTC-Pad2)") (class "Default")
      (node (ref "U1") (pin "2") (pinfunction "PC13-TAMPER-RTC_2") (pintype "bidirectional"))
    )
    (net (code "63") (name "unconnected-(U1-PC14-OSC32_IN-Pad3)") (class "Default")
      (node (ref "U1") (pin "3") (pinfunction "PC14-OSC32_IN_3") (pintype "bidirectional"))
    )
    (net (code "64") (name "unconnected-(U1-PC15-OSC32_OUT-Pad4)") (class "Default")
      (node (ref "U1") (pin "4") (pinfunction "PC15-OSC32_OUT_4") (pintype "bidirectional"))
    )
    (net (code "65") (name "unconnected-(U1-VBAT-Pad1)") (class "Default")
      (node (ref "U1") (pin "1") (pinfunction "VBAT_1") (pintype "passive"))
    )
    (net (code "66") (name "~{EMS}") (class "Default")
      (node (ref "U1") (pin "11") (pinfunction "PA1_11") (pintype "bidirectional"))
      (node (ref "U6") (pin "3") (pinfunction "EMIT_3") (pintype "passive"))
    )
    (net (code "67") (name "~{RESET}") (class "Default")
      (node (ref "C14") (pin "2") (pinfunction "2_2") (pintype "passive"))
      (node (ref "S1") (pin "P$2") (pinfunction "2_P$2") (pintype "bidirectional"))
      (node (ref "U1") (pin "7") (pinfunction "NRST_7") (pintype "bidirectional"))
    )
  )
)
